# Senior_Receiver.net
KiCad netlist of a schematic drawn in EasyEDA
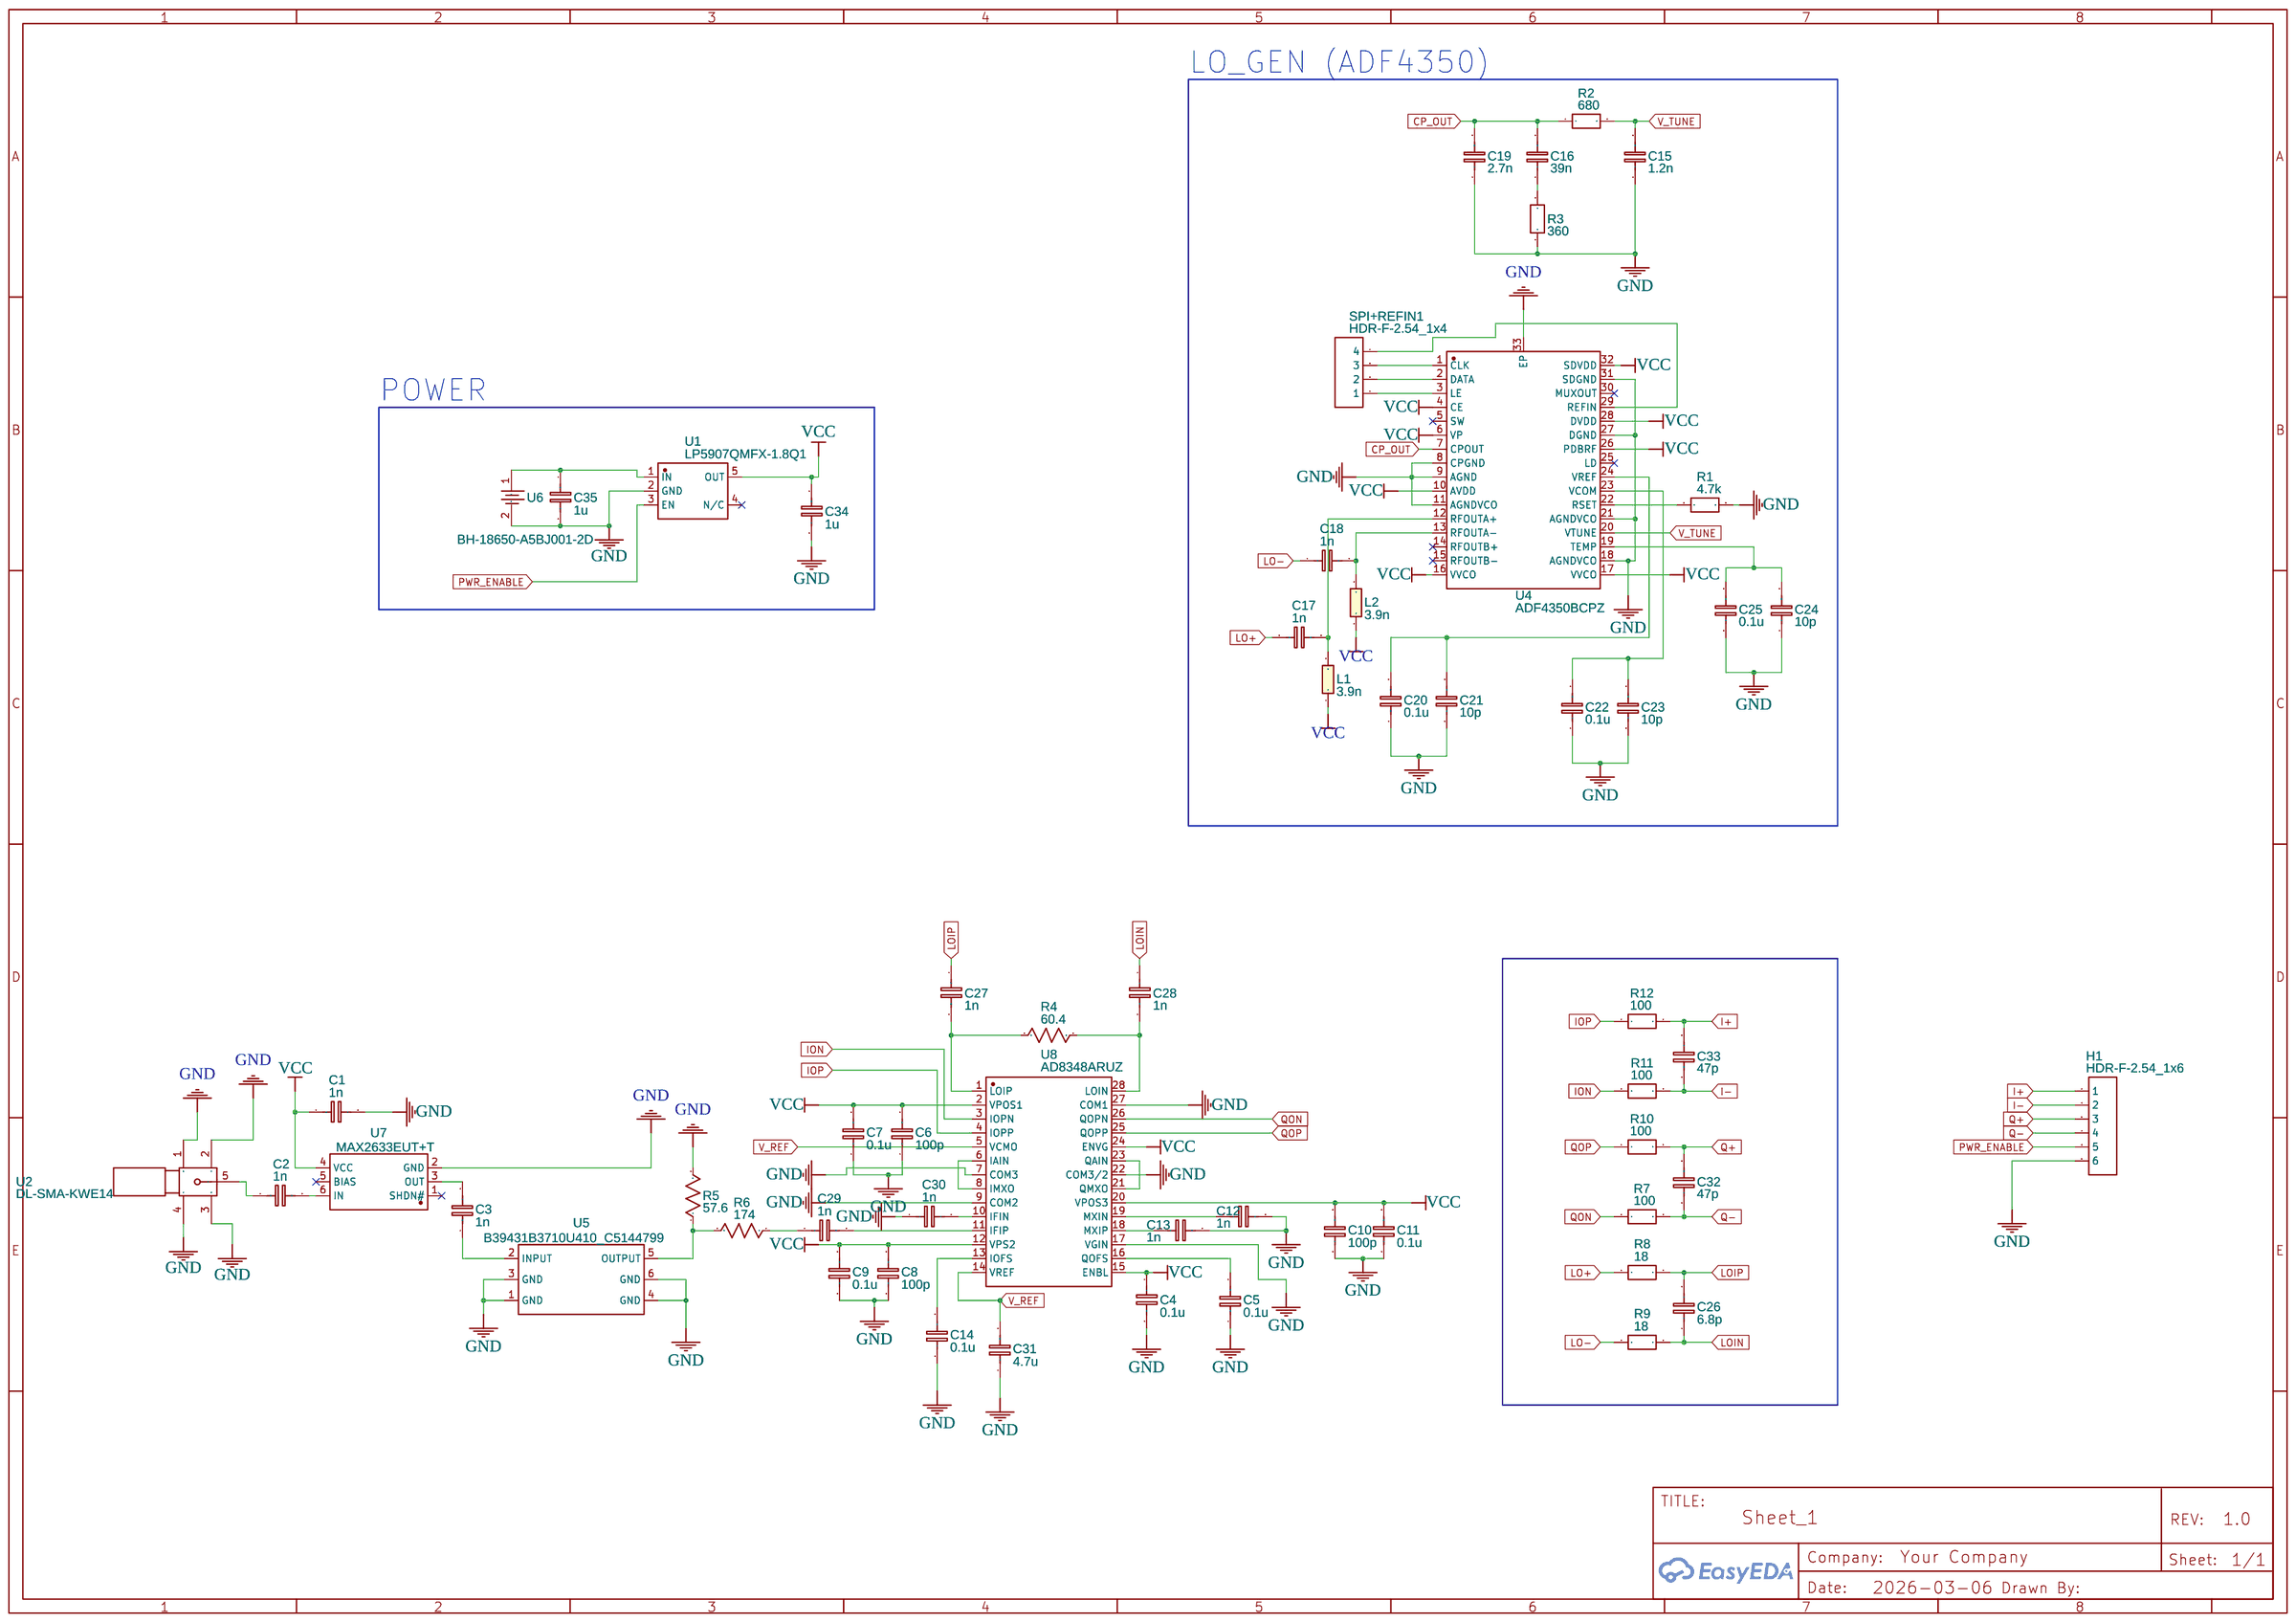
[diagram p0: schematic sheet]

(export (version "E")
  (design (tool "Eeschema 10.0.6"))
  (components
    (comp (ref "C1") (value "1n") (libsource (lib "") (part "C_0603_EU_6")))
    (comp (ref "C2") (value "1n") (libsource (lib "") (part "C_0603_EU_6")))
    (comp (ref "C3") (value "1n") (libsource (lib "") (part "C_0603_EU_5")))
    (comp (ref "C4") (value "0.1u") (libsource (lib "") (part "C_0603_EU_3")))
    (comp (ref "C5") (value "0.1u") (libsource (lib "") (part "C_0603_EU")))
    (comp (ref "C6") (value "100p") (libsource (lib "") (part "C_0603_EU")))
    (comp (ref "C7") (value "0.1u") (libsource (lib "") (part "C_0603_EU")))
    (comp (ref "C8") (value "100p") (libsource (lib "") (part "C_0603_EU")))
    (comp (ref "C9") (value "0.1u") (libsource (lib "") (part "C_0603_EU")))
    (comp (ref "C10") (value "100p") (libsource (lib "") (part "C_0603_EU")))
    (comp (ref "C11") (value "0.1u") (libsource (lib "") (part "C_0603_EU")))
    (comp (ref "C12") (value "1n") (libsource (lib "") (part "C_0603_EU_2")))
    (comp (ref "C13") (value "1n") (libsource (lib "") (part "C_0603_EU_2")))
    (comp (ref "C14") (value "0.1u") (libsource (lib "") (part "C_0603_EU")))
    (comp (ref "C15") (value "1.2n") (libsource (lib "") (part "C_0603_EU_1")))
    (comp (ref "C16") (value "39n") (libsource (lib "") (part "C_0603_EU_1")))
    (comp (ref "C17") (value "1n") (libsource (lib "") (part "C_0603_EU_4")))
    (comp (ref "C18") (value "1n") (libsource (lib "") (part "C_0603_EU_4")))
    (comp (ref "C19") (value "2.7n") (libsource (lib "") (part "C_0603_EU_1")))
    (comp (ref "C20") (value "0.1u") (libsource (lib "") (part "C_0603_EU_1")))
    (comp (ref "C21") (value "10p") (libsource (lib "") (part "C_0603_EU_1")))
    (comp (ref "C22") (value "0.1u") (libsource (lib "") (part "C_0603_EU_1")))
    (comp (ref "C23") (value "10p") (libsource (lib "") (part "C_0603_EU_1")))
    (comp (ref "C24") (value "10p") (libsource (lib "") (part "C_0603_EU_1")))
    (comp (ref "C25") (value "0.1u") (libsource (lib "") (part "C_0603_EU_1")))
    (comp (ref "C26") (value "6.8p") (libsource (lib "") (part "C_0402_EU")))
    (comp (ref "C27") (value "1n") (libsource (lib "") (part "C_0603_EU_3")))
    (comp (ref "C28") (value "1n") (libsource (lib "") (part "C_0603_EU_3")))
    (comp (ref "C29") (value "1n") (libsource (lib "") (part "C_0603_EU_2")))
    (comp (ref "C30") (value "1n") (libsource (lib "") (part "C_0603_EU_2")))
    (comp (ref "C31") (value "4.7u") (libsource (lib "") (part "C_0603_EU")))
    (comp (ref "C32") (value "47p") (libsource (lib "") (part "C_0603_EU")))
    (comp (ref "C33") (value "47p") (libsource (lib "") (part "C_0603_EU")))
    (comp (ref "C34") (value "1u") (libsource (lib "") (part "C_0603_EU_8")))
    (comp (ref "C35") (value "1u") (libsource (lib "") (part "C_0603_EU_7")))
    (comp (ref "H1") (value "HDR-F-2.54_1x6") (libsource (lib "") (part "HDR-F-2.54_1x6")))
    (comp (ref "L1") (value "3.9n") (libsource (lib "") (part "L0603_EU")))
    (comp (ref "L2") (value "3.9n") (libsource (lib "") (part "L0603_EU")))
    (comp (ref "R1") (value "4.7k") (libsource (lib "") (part "R_0603_EU")))
    (comp (ref "R2") (value "680") (libsource (lib "") (part "R_0603_EU")))
    (comp (ref "R3") (value "360") (libsource (lib "") (part "R_0603_EU_1")))
    (comp (ref "R4") (value "60.4") (libsource (lib "") (part "R_0603_US_1")))
    (comp (ref "R5") (value "57.6") (libsource (lib "") (part "R_0603_US")))
    (comp (ref "R6") (value "174") (libsource (lib "") (part "R_0603_US_2")))
    (comp (ref "R7") (value "100") (libsource (lib "") (part "R_0603_EU")))
    (comp (ref "R8") (value "18") (libsource (lib "") (part "R_0402_EU")))
    (comp (ref "R9") (value "18") (libsource (lib "") (part "R_0402_EU")))
    (comp (ref "R10") (value "100") (libsource (lib "") (part "R_0603_EU")))
    (comp (ref "R11") (value "100") (libsource (lib "") (part "R_0603_EU")))
    (comp (ref "R12") (value "100") (libsource (lib "") (part "R_0603_EU")))
    (comp (ref "SPI+REFIN1") (value "HDR-F-2.54_1x4") (libsource (lib "") (part "HDR-F-2.54_1x4")))
    (comp (ref "U1")
      (value "LP5907QMFX-1.8Q1")
      (fields (field (name "Manufacturer") "TI(德州仪器)"))
      (libsource (lib "") (part "LP5907QMFX-1.8Q1"))
    )
    (comp (ref "U2")
      (value "DL-SMA-KWE14")
      (fields (field (name "Manufacturer") "DEALON(德艺隆)"))
      (libsource (lib "") (part "DL-SMA-KWE14"))
    )
    (comp (ref "U4")
      (value "ADF4350BCPZ")
      (fields (field (name "Manufacturer") "ADI(亚德诺)"))
      (libsource (lib "") (part "ADF4350BCPZ"))
    )
    (comp (ref "U5")
      (value "B39431B3710U410_C5144799")
      (fields (field (name "Manufacturer Part") "B39431B3710U410"))
      (libsource (lib "") (part "B39431B3710U410_C5144799"))
    )
    (comp (ref "U6")
      (value "BH-18650-A5BJ001-2D")
      (fields (field (name "Manufacturer") "MYOUNG(美阳)"))
      (libsource (lib "") (part "BH-18650-A5BJ001-2D"))
    )
    (comp (ref "U7")
      (value "MAX2633EUT+T")
      (fields (field (name "Manufacturer") "ADI(亚德诺)/MAXIM(美信)"))
      (libsource (lib "") (part "MAX2633EUT+T"))
    )
    (comp (ref "U8")
      (value "AD8348ARUZ")
      (fields (field (name "Manufacturer") "ADI(亚德诺)"))
      (libsource (lib "") (part "AD8348ARUZ"))
    )
  )
  (nets
    (net (code "1") (name "CP_OUT") (class "Default")
      (node (ref "C16") (pin "2") (pinfunction "2_2") (pintype "unspecified"))
      (node (ref "C19") (pin "2") (pinfunction "2_2") (pintype "unspecified"))
      (node (ref "R2") (pin "1") (pinfunction "1_1") (pintype "unspecified"))
      (node (ref "U4") (pin "7") (pinfunction "CPOUT_7") (pintype "unspecified"))
    )
    (net (code "2") (name "GND") (class "Default")
      (node (ref "C1") (pin "2") (pinfunction "2_2") (pintype "unspecified"))
      (node (ref "C10") (pin "1") (pinfunction "1_1") (pintype "unspecified"))
      (node (ref "C11") (pin "1") (pinfunction "1_1") (pintype "unspecified"))
      (node (ref "C12") (pin "2") (pinfunction "2_2") (pintype "unspecified"))
      (node (ref "C13") (pin "2") (pinfunction "2_2") (pintype "unspecified"))
      (node (ref "C14") (pin "1") (pinfunction "1_1") (pintype "unspecified"))
      (node (ref "C15") (pin "1") (pinfunction "1_1") (pintype "unspecified"))
      (node (ref "C19") (pin "1") (pinfunction "1_1") (pintype "unspecified"))
      (node (ref "C20") (pin "1") (pinfunction "1_1") (pintype "unspecified"))
      (node (ref "C21") (pin "1") (pinfunction "1_1") (pintype "unspecified"))
      (node (ref "C22") (pin "1") (pinfunction "1_1") (pintype "unspecified"))
      (node (ref "C23") (pin "1") (pinfunction "1_1") (pintype "unspecified"))
      (node (ref "C24") (pin "1") (pinfunction "1_1") (pintype "unspecified"))
      (node (ref "C25") (pin "1") (pinfunction "1_1") (pintype "unspecified"))
      (node (ref "C30") (pin "1") (pinfunction "1_1") (pintype "unspecified"))
      (node (ref "C31") (pin "1") (pinfunction "1_1") (pintype "unspecified"))
      (node (ref "C34") (pin "2") (pinfunction "2_2") (pintype "unspecified"))
      (node (ref "C35") (pin "2") (pinfunction "2_2") (pintype "unspecified"))
      (node (ref "C4") (pin "2") (pinfunction "2_2") (pintype "unspecified"))
      (node (ref "C5") (pin "1") (pinfunction "1_1") (pintype "unspecified"))
      (node (ref "C6") (pin "1") (pinfunction "1_1") (pintype "unspecified"))
      (node (ref "C7") (pin "1") (pinfunction "1_1") (pintype "unspecified"))
      (node (ref "C8") (pin "1") (pinfunction "1_1") (pintype "unspecified"))
      (node (ref "C9") (pin "1") (pinfunction "1_1") (pintype "unspecified"))
      (node (ref "H1") (pin "6") (pinfunction "6_6") (pintype "input"))
      (node (ref "R1") (pin "2") (pinfunction "2_2") (pintype "unspecified"))
      (node (ref "R3") (pin "1") (pinfunction "1_1") (pintype "unspecified"))
      (node (ref "R5") (pin "2") (pinfunction "2_2") (pintype "unspecified"))
      (node (ref "U1") (pin "2") (pinfunction "GND_2") (pintype "unspecified"))
      (node (ref "U2") (pin "1") (pinfunction "1_1") (pintype "unspecified"))
      (node (ref "U2") (pin "2") (pinfunction "2_2") (pintype "unspecified"))
      (node (ref "U2") (pin "3") (pinfunction "3_3") (pintype "unspecified"))
      (node (ref "U2") (pin "4") (pinfunction "4_4") (pintype "unspecified"))
      (node (ref "U4") (pin "11") (pinfunction "AGNDVCO_11") (pintype "unspecified"))
      (node (ref "U4") (pin "18") (pinfunction "AGNDVCO_18") (pintype "unspecified"))
      (node (ref "U4") (pin "21") (pinfunction "AGNDVCO_21") (pintype "unspecified"))
      (node (ref "U4") (pin "27") (pinfunction "DGND_27") (pintype "unspecified"))
      (node (ref "U4") (pin "31") (pinfunction "SDGND_31") (pintype "unspecified"))
      (node (ref "U4") (pin "33") (pinfunction "EP_33") (pintype "unspecified"))
      (node (ref "U4") (pin "8") (pinfunction "CPGND_8") (pintype "unspecified"))
      (node (ref "U4") (pin "9") (pinfunction "AGND_9") (pintype "unspecified"))
      (node (ref "U5") (pin "1") (pinfunction "GND_1") (pintype "unspecified"))
      (node (ref "U5") (pin "3") (pinfunction "GND_3") (pintype "unspecified"))
      (node (ref "U5") (pin "4") (pinfunction "GND_4") (pintype "unspecified"))
      (node (ref "U5") (pin "6") (pinfunction "GND_6") (pintype "unspecified"))
      (node (ref "U6") (pin "2") (pinfunction "2_2") (pintype "input"))
      (node (ref "U7") (pin "2") (pinfunction "GND_2") (pintype "unspecified"))
      (node (ref "U8") (pin "17") (pinfunction "VGIN_17") (pintype "unspecified"))
      (node (ref "U8") (pin "22") (pinfunction "COM3/2_22") (pintype "unspecified"))
      (node (ref "U8") (pin "27") (pinfunction "COM1_27") (pintype "unspecified"))
      (node (ref "U8") (pin "7") (pinfunction "COM3_7") (pintype "unspecified"))
      (node (ref "U8") (pin "9") (pinfunction "COM2_9") (pintype "unspecified"))
    )
    (net (code "3") (name "I+") (class "Default")
      (node (ref "C33") (pin "2") (pinfunction "2_2") (pintype "unspecified"))
      (node (ref "H1") (pin "1") (pinfunction "1_1") (pintype "input"))
      (node (ref "R12") (pin "2") (pinfunction "2_2") (pintype "unspecified"))
    )
    (net (code "4") (name "I-") (class "Default")
      (node (ref "C33") (pin "1") (pinfunction "1_1") (pintype "unspecified"))
      (node (ref "H1") (pin "2") (pinfunction "2_2") (pintype "input"))
      (node (ref "R11") (pin "2") (pinfunction "2_2") (pintype "unspecified"))
    )
    (net (code "5") (name "ION") (class "Default")
      (node (ref "R11") (pin "1") (pinfunction "1_1") (pintype "unspecified"))
      (node (ref "U8") (pin "3") (pinfunction "IOPN_3") (pintype "unspecified"))
    )
    (net (code "6") (name "IOP") (class "Default")
      (node (ref "R12") (pin "1") (pinfunction "1_1") (pintype "unspecified"))
      (node (ref "U8") (pin "4") (pinfunction "IOPP_4") (pintype "unspecified"))
    )
    (net (code "7") (name "LO+") (class "Default")
      (node (ref "C17") (pin "1") (pinfunction "1_1") (pintype "unspecified"))
      (node (ref "R8") (pin "1") (pinfunction "1_1") (pintype "unspecified"))
    )
    (net (code "8") (name "LO-") (class "Default")
      (node (ref "C18") (pin "1") (pinfunction "1_1") (pintype "unspecified"))
      (node (ref "R9") (pin "1") (pinfunction "1_1") (pintype "unspecified"))
    )
    (net (code "9") (name "LOIN") (class "Default")
      (node (ref "C26") (pin "1") (pinfunction "1_1") (pintype "unspecified"))
      (node (ref "C28") (pin "1") (pinfunction "1_1") (pintype "unspecified"))
      (node (ref "R9") (pin "2") (pinfunction "2_2") (pintype "unspecified"))
    )
    (net (code "10") (name "LOIP") (class "Default")
      (node (ref "C26") (pin "2") (pinfunction "2_2") (pintype "unspecified"))
      (node (ref "C27") (pin "1") (pinfunction "1_1") (pintype "unspecified"))
      (node (ref "R8") (pin "2") (pinfunction "2_2") (pintype "unspecified"))
    )
    (net (code "11") (name "Net-(C2-Pad1)") (class "Default")
      (node (ref "C2") (pin "1") (pinfunction "1_1") (pintype "unspecified"))
      (node (ref "U2") (pin "5") (pinfunction "5_5") (pintype "unspecified"))
    )
    (net (code "12") (name "Net-(C16-Pad1)") (class "Default")
      (node (ref "C16") (pin "1") (pinfunction "1_1") (pintype "unspecified"))
      (node (ref "R3") (pin "2") (pinfunction "2_2") (pintype "unspecified"))
    )
    (net (code "13") (name "Net-(C29-Pad1)") (class "Default")
      (node (ref "C29") (pin "1") (pinfunction "1_1") (pintype "unspecified"))
      (node (ref "R6") (pin "1") (pinfunction "1_1") (pintype "unspecified"))
    )
    (net (code "14") (name "Net-(U1-IN)") (class "Default")
      (node (ref "C35") (pin "1") (pinfunction "1_1") (pintype "unspecified"))
      (node (ref "U1") (pin "1") (pinfunction "IN_1") (pintype "unspecified"))
      (node (ref "U6") (pin "1") (pinfunction "1_1") (pintype "input"))
    )
    (net (code "15") (name "Net-(U4-CLK)") (class "Default")
      (node (ref "SPI+REFIN1") (pin "3") (pinfunction "3_3") (pintype "unspecified"))
      (node (ref "U4") (pin "1") (pinfunction "CLK_1") (pintype "unspecified"))
    )
    (net (code "16") (name "Net-(U4-DATA)") (class "Default")
      (node (ref "SPI+REFIN1") (pin "2") (pinfunction "2_2") (pintype "unspecified"))
      (node (ref "U4") (pin "2") (pinfunction "DATA_2") (pintype "unspecified"))
    )
    (net (code "17") (name "Net-(U4-LE)") (class "Default")
      (node (ref "SPI+REFIN1") (pin "1") (pinfunction "1_1") (pintype "unspecified"))
      (node (ref "U4") (pin "3") (pinfunction "LE_3") (pintype "unspecified"))
    )
    (net (code "18") (name "Net-(U4-REFIN)") (class "Default")
      (node (ref "SPI+REFIN1") (pin "4") (pinfunction "4_4") (pintype "unspecified"))
      (node (ref "U4") (pin "29") (pinfunction "REFIN_29") (pintype "unspecified"))
    )
    (net (code "19") (name "Net-(U4-RFOUTA+)") (class "Default")
      (node (ref "C17") (pin "2") (pinfunction "2_2") (pintype "unspecified"))
      (node (ref "L1") (pin "2") (pinfunction "2_2") (pintype "unspecified"))
      (node (ref "U4") (pin "12") (pinfunction "RFOUTA+_12") (pintype "unspecified"))
    )
    (net (code "20") (name "Net-(U4-RFOUTA-)") (class "Default")
      (node (ref "C18") (pin "2") (pinfunction "2_2") (pintype "unspecified"))
      (node (ref "L2") (pin "2") (pinfunction "2_2") (pintype "unspecified"))
      (node (ref "U4") (pin "13") (pinfunction "RFOUTA-_13") (pintype "unspecified"))
    )
    (net (code "21") (name "Net-(U4-RSET)") (class "Default")
      (node (ref "R1") (pin "1") (pinfunction "1_1") (pintype "unspecified"))
      (node (ref "U4") (pin "22") (pinfunction "RSET_22") (pintype "unspecified"))
    )
    (net (code "22") (name "Net-(U4-TEMP)") (class "Default")
      (node (ref "C24") (pin "2") (pinfunction "2_2") (pintype "unspecified"))
      (node (ref "C25") (pin "2") (pinfunction "2_2") (pintype "unspecified"))
      (node (ref "U4") (pin "19") (pinfunction "TEMP_19") (pintype "unspecified"))
    )
    (net (code "23") (name "Net-(U4-VCOM)") (class "Default")
      (node (ref "C22") (pin "2") (pinfunction "2_2") (pintype "unspecified"))
      (node (ref "C23") (pin "2") (pinfunction "2_2") (pintype "unspecified"))
      (node (ref "U4") (pin "23") (pinfunction "VCOM_23") (pintype "unspecified"))
    )
    (net (code "24") (name "Net-(U4-VREF)") (class "Default")
      (node (ref "C20") (pin "2") (pinfunction "2_2") (pintype "unspecified"))
      (node (ref "C21") (pin "2") (pinfunction "2_2") (pintype "unspecified"))
      (node (ref "U4") (pin "24") (pinfunction "VREF_24") (pintype "unspecified"))
    )
    (net (code "25") (name "Net-(U5-INPUT)") (class "Default")
      (node (ref "C3") (pin "1") (pinfunction "1_1") (pintype "unspecified"))
      (node (ref "U5") (pin "2") (pinfunction "INPUT_2") (pintype "unspecified"))
    )
    (net (code "26") (name "Net-(U5-OUTPUT)") (class "Default")
      (node (ref "R5") (pin "1") (pinfunction "1_1") (pintype "unspecified"))
      (node (ref "R6") (pin "2") (pinfunction "2_2") (pintype "unspecified"))
      (node (ref "U5") (pin "5") (pinfunction "OUTPUT_5") (pintype "unspecified"))
    )
    (net (code "27") (name "Net-(U7-IN)") (class "Default")
      (node (ref "C2") (pin "2") (pinfunction "2_2") (pintype "unspecified"))
      (node (ref "U7") (pin "6") (pinfunction "IN_6") (pintype "unspecified"))
    )
    (net (code "28") (name "Net-(U7-OUT)") (class "Default")
      (node (ref "C3") (pin "2") (pinfunction "2_2") (pintype "unspecified"))
      (node (ref "U7") (pin "3") (pinfunction "OUT_3") (pintype "unspecified"))
    )
    (net (code "29") (name "Net-(U8-IAIN)") (class "Default")
      (node (ref "U8") (pin "6") (pinfunction "IAIN_6") (pintype "unspecified"))
      (node (ref "U8") (pin "8") (pinfunction "IMXO_8") (pintype "unspecified"))
    )
    (net (code "30") (name "Net-(U8-IFIN)") (class "Default")
      (node (ref "C30") (pin "2") (pinfunction "2_2") (pintype "unspecified"))
      (node (ref "U8") (pin "10") (pinfunction "IFIN_10") (pintype "unspecified"))
    )
    (net (code "31") (name "Net-(U8-IFIP)") (class "Default")
      (node (ref "C29") (pin "2") (pinfunction "2_2") (pintype "unspecified"))
      (node (ref "U8") (pin "11") (pinfunction "IFIP_11") (pintype "unspecified"))
    )
    (net (code "32") (name "Net-(U8-IOFS)") (class "Default")
      (node (ref "C14") (pin "2") (pinfunction "2_2") (pintype "unspecified"))
      (node (ref "U8") (pin "13") (pinfunction "IOFS_13") (pintype "unspecified"))
    )
    (net (code "33") (name "Net-(U8-LOIN)") (class "Default")
      (node (ref "C28") (pin "2") (pinfunction "2_2") (pintype "unspecified"))
      (node (ref "R4") (pin "2") (pinfunction "2_2") (pintype "unspecified"))
      (node (ref "U8") (pin "28") (pinfunction "LOIN_28") (pintype "unspecified"))
    )
    (net (code "34") (name "Net-(U8-LOIP)") (class "Default")
      (node (ref "C27") (pin "2") (pinfunction "2_2") (pintype "unspecified"))
      (node (ref "R4") (pin "1") (pinfunction "1_1") (pintype "unspecified"))
      (node (ref "U8") (pin "1") (pinfunction "LOIP_1") (pintype "unspecified"))
    )
    (net (code "35") (name "Net-(U8-MXIN)") (class "Default")
      (node (ref "C12") (pin "1") (pinfunction "1_1") (pintype "unspecified"))
      (node (ref "U8") (pin "19") (pinfunction "MXIN_19") (pintype "unspecified"))
    )
    (net (code "36") (name "Net-(U8-MXIP)") (class "Default")
      (node (ref "C13") (pin "1") (pinfunction "1_1") (pintype "unspecified"))
      (node (ref "U8") (pin "18") (pinfunction "MXIP_18") (pintype "unspecified"))
    )
    (net (code "37") (name "Net-(U8-QAIN)") (class "Default")
      (node (ref "U8") (pin "21") (pinfunction "QMXO_21") (pintype "unspecified"))
      (node (ref "U8") (pin "23") (pinfunction "QAIN_23") (pintype "unspecified"))
    )
    (net (code "38") (name "Net-(U8-QOFS)") (class "Default")
      (node (ref "C5") (pin "2") (pinfunction "2_2") (pintype "unspecified"))
      (node (ref "U8") (pin "16") (pinfunction "QOFS_16") (pintype "unspecified"))
    )
    (net (code "39") (name "PWR_ENABLE") (class "Default")
      (node (ref "H1") (pin "5") (pinfunction "5_5") (pintype "input"))
      (node (ref "U1") (pin "3") (pinfunction "EN_3") (pintype "unspecified"))
    )
    (net (code "40") (name "Q+") (class "Default")
      (node (ref "C32") (pin "2") (pinfunction "2_2") (pintype "unspecified"))
      (node (ref "H1") (pin "3") (pinfunction "3_3") (pintype "input"))
      (node (ref "R10") (pin "2") (pinfunction "2_2") (pintype "unspecified"))
    )
    (net (code "41") (name "Q-") (class "Default")
      (node (ref "C32") (pin "1") (pinfunction "1_1") (pintype "unspecified"))
      (node (ref "H1") (pin "4") (pinfunction "4_4") (pintype "input"))
      (node (ref "R7") (pin "2") (pinfunction "2_2") (pintype "unspecified"))
    )
    (net (code "42") (name "QON") (class "Default")
      (node (ref "R7") (pin "1") (pinfunction "1_1") (pintype "unspecified"))
      (node (ref "U8") (pin "26") (pinfunction "QOPN_26") (pintype "unspecified"))
    )
    (net (code "43") (name "QOP") (class "Default")
      (node (ref "R10") (pin "1") (pinfunction "1_1") (pintype "unspecified"))
      (node (ref "U8") (pin "25") (pinfunction "QOPP_25") (pintype "unspecified"))
    )
    (net (code "44") (name "VCC") (class "Default")
      (node (ref "C1") (pin "1") (pinfunction "1_1") (pintype "unspecified"))
      (node (ref "C10") (pin "2") (pinfunction "2_2") (pintype "unspecified"))
      (node (ref "C11") (pin "2") (pinfunction "2_2") (pintype "unspecified"))
      (node (ref "C34") (pin "1") (pinfunction "1_1") (pintype "unspecified"))
      (node (ref "C4") (pin "1") (pinfunction "1_1") (pintype "unspecified"))
      (node (ref "C6") (pin "2") (pinfunction "2_2") (pintype "unspecified"))
      (node (ref "C7") (pin "2") (pinfunction "2_2") (pintype "unspecified"))
      (node (ref "C8") (pin "2") (pinfunction "2_2") (pintype "unspecified"))
      (node (ref "C9") (pin "2") (pinfunction "2_2") (pintype "unspecified"))
      (node (ref "L1") (pin "1") (pinfunction "1_1") (pintype "unspecified"))
      (node (ref "L2") (pin "1") (pinfunction "1_1") (pintype "unspecified"))
      (node (ref "U1") (pin "5") (pinfunction "OUT_5") (pintype "unspecified"))
      (node (ref "U4") (pin "10") (pinfunction "AVDD_10") (pintype "unspecified"))
      (node (ref "U4") (pin "16") (pinfunction "VVCO_16") (pintype "unspecified"))
      (node (ref "U4") (pin "17") (pinfunction "VVCO_17") (pintype "unspecified"))
      (node (ref "U4") (pin "26") (pinfunction "PDBRF_26") (pintype "unspecified"))
      (node (ref "U4") (pin "28") (pinfunction "DVDD_28") (pintype "unspecified"))
      (node (ref "U4") (pin "32") (pinfunction "SDVDD_32") (pintype "unspecified"))
      (node (ref "U4") (pin "4") (pinfunction "CE_4") (pintype "unspecified"))
      (node (ref "U4") (pin "6") (pinfunction "VP_6") (pintype "unspecified"))
      (node (ref "U7") (pin "4") (pinfunction "VCC_4") (pintype "unspecified"))
      (node (ref "U8") (pin "12") (pinfunction "VPS2_12") (pintype "unspecified"))
      (node (ref "U8") (pin "15") (pinfunction "ENBL_15") (pintype "unspecified"))
      (node (ref "U8") (pin "2") (pinfunction "VPOS1_2") (pintype "unspecified"))
      (node (ref "U8") (pin "20") (pinfunction "VPOS3_20") (pintype "unspecified"))
      (node (ref "U8") (pin "24") (pinfunction "ENVG_24") (pintype "unspecified"))
    )
    (net (code "45") (name "V_REF") (class "Default")
      (node (ref "C31") (pin "2") (pinfunction "2_2") (pintype "unspecified"))
      (node (ref "U8") (pin "14") (pinfunction "VREF_14") (pintype "unspecified"))
      (node (ref "U8") (pin "5") (pinfunction "VCMO_5") (pintype "unspecified"))
    )
    (net (code "46") (name "V_TUNE") (class "Default")
      (node (ref "C15") (pin "2") (pinfunction "2_2") (pintype "unspecified"))
      (node (ref "R2") (pin "2") (pinfunction "2_2") (pintype "unspecified"))
      (node (ref "U4") (pin "20") (pinfunction "VTUNE_20") (pintype "unspecified"))
    )
    (net (code "47") (name "unconnected-(U1-N{slash}C-Pad4)") (class "Default")
      (node (ref "U1") (pin "4") (pinfunction "N/C_4") (pintype "unspecified+no_connect"))
    )
    (net (code "48") (name "unconnected-(U4-LD-Pad25)") (class "Default")
      (node (ref "U4") (pin "25") (pinfunction "LD_25") (pintype "unspecified+no_connect"))
    )
    (net (code "49") (name "unconnected-(U4-MUXOUT-Pad30)") (class "Default")
      (node (ref "U4") (pin "30") (pinfunction "MUXOUT_30") (pintype "unspecified+no_connect"))
    )
    (net (code "50") (name "unconnected-(U4-RFOUTB+-Pad14)") (class "Default")
      (node (ref "U4") (pin "14") (pinfunction "RFOUTB+_14") (pintype "unspecified+no_connect"))
    )
    (net (code "51") (name "unconnected-(U4-RFOUTB--Pad15)") (class "Default")
      (node (ref "U4") (pin "15") (pinfunction "RFOUTB-_15") (pintype "unspecified+no_connect"))
    )
    (net (code "52") (name "unconnected-(U4-SW-Pad5)") (class "Default")
      (node (ref "U4") (pin "5") (pinfunction "SW_5") (pintype "unspecified+no_connect"))
    )
    (net (code "53") (name "unconnected-(U7-BIAS-Pad5)") (class "Default")
      (node (ref "U7") (pin "5") (pinfunction "BIAS_5") (pintype "unspecified+no_connect"))
    )
    (net (code "54") (name "unconnected-(U7-SHDN#-Pad1)") (class "Default")
      (node (ref "U7") (pin "1") (pinfunction "SHDN#_1") (pintype "unspecified+no_connect"))
    )
  )
)
